# clock_motherboard.net
KiCad netlist of a schematic drawn in EAGLE
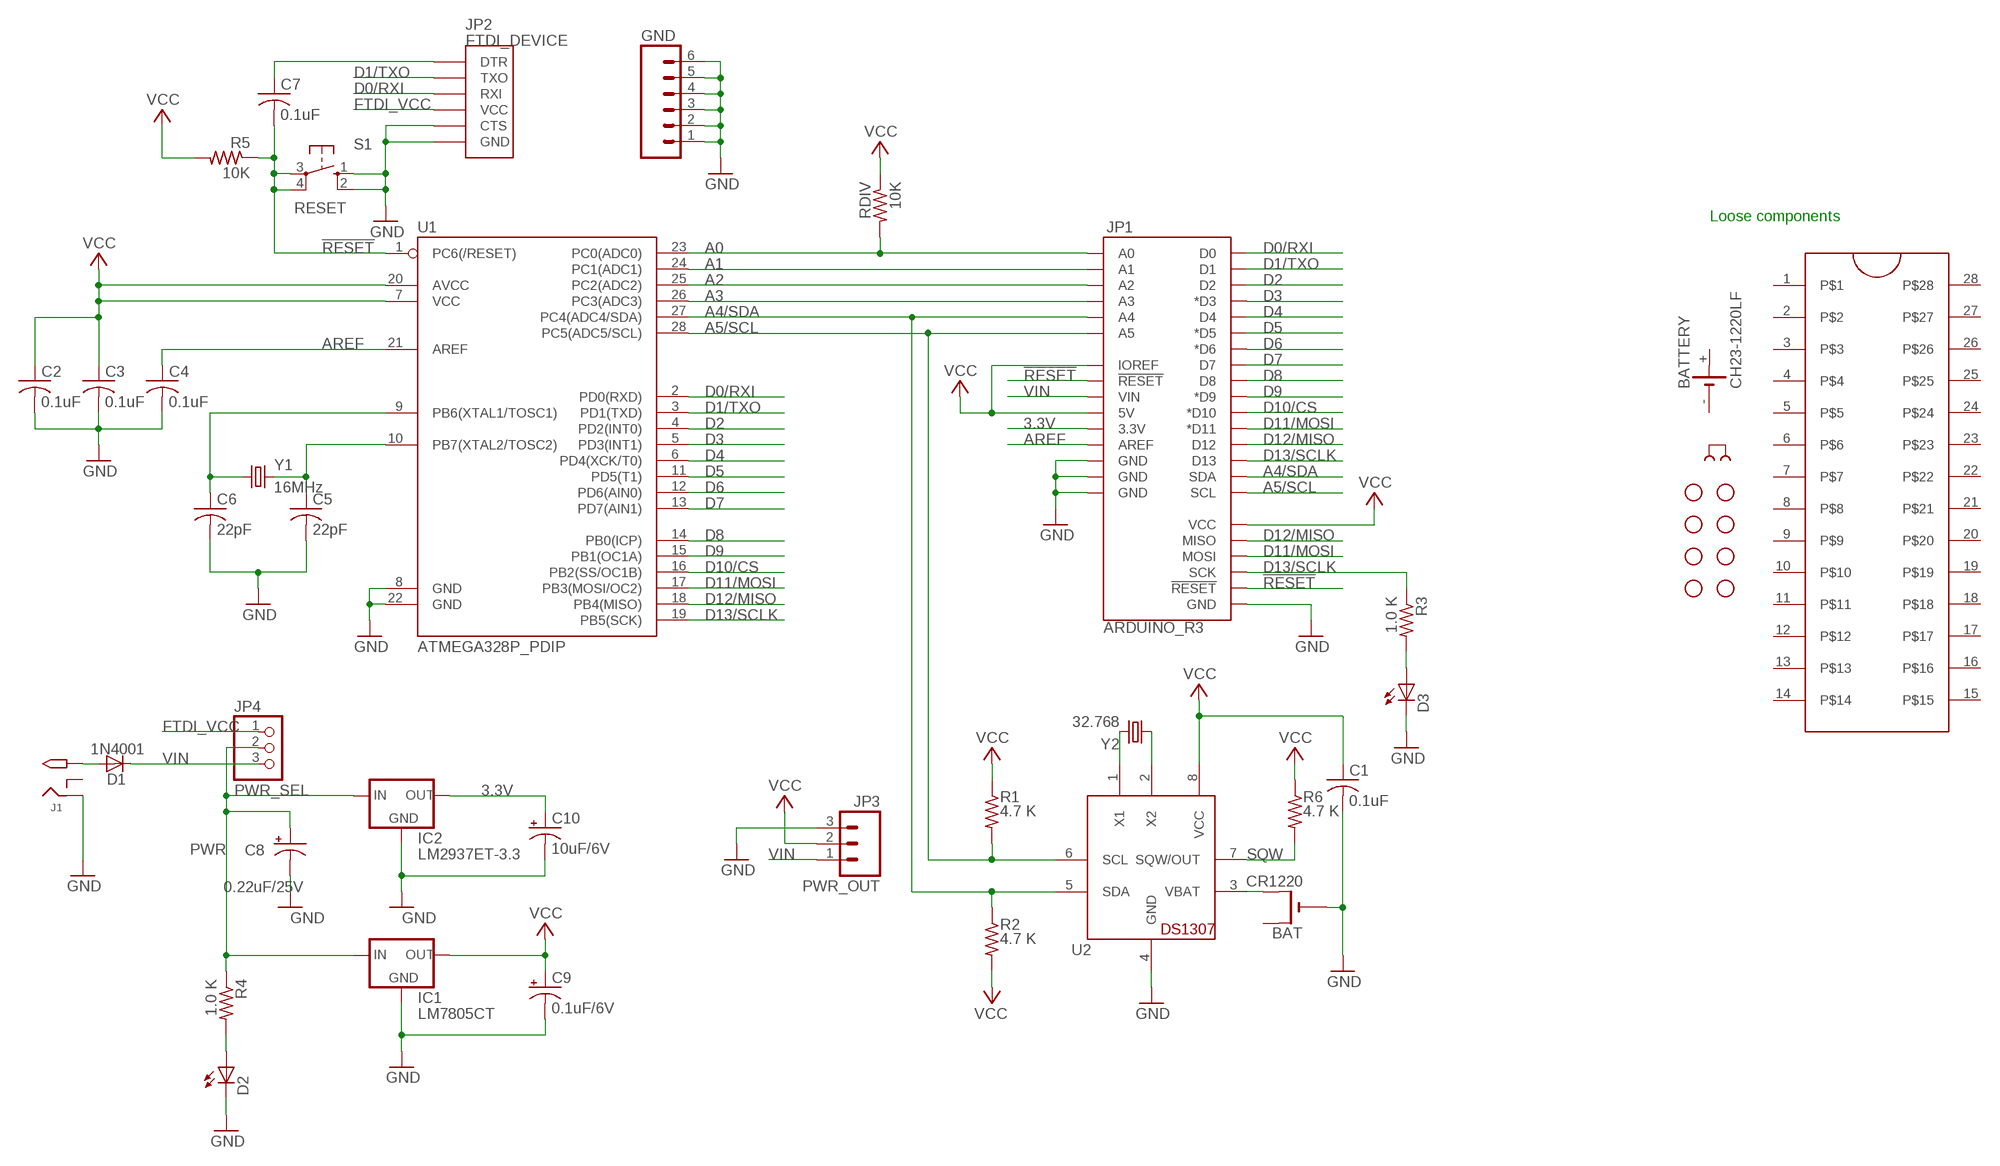
[diagram p0: schematic, sheet 1]

(export (version "E")
  (design (tool "Eeschema 10.0.6"))
  (components
    (comp (ref "BAT")
      (value "CR1220")
      (footprint "eagle-import:CR1220-THM")
      (fields (field (name "PARTNO") "3001"))
      (libsource (lib "eagle-import") (part "CR1220THM"))
    )
    (comp (ref "BATTERY")
      (value "CH23-1220LF")
      (footprint "eagle-import:CH23-1220LF")
      (fields (field (name "PARTNO") "CR1220"))
      (libsource (lib "eagle-import") (part "CH23-1220LF"))
    )
    (comp (ref "C1")
      (value "0.1uF")
      (footprint "eagle-import:C025-025X050")
      (fields (field (name "PARTNO") "21RZ310-RC"))
      (libsource (lib "eagle-import") (part "C-US025-025X050"))
    )
    (comp (ref "C2")
      (value "0.1uF")
      (footprint "eagle-import:C025-025X050")
      (fields (field (name "PARTNO") "21RZ310-RC"))
      (libsource (lib "eagle-import") (part "C-US025-025X050"))
    )
    (comp (ref "C3")
      (value "0.1uF")
      (footprint "eagle-import:C025-025X050")
      (fields (field (name "PARTNO") "21RZ310-RC"))
      (libsource (lib "eagle-import") (part "C-US025-025X050"))
    )
    (comp (ref "C4")
      (value "0.1uF")
      (footprint "eagle-import:C025-025X050")
      (fields (field (name "PARTNO") "21RZ310-RC"))
      (libsource (lib "eagle-import") (part "C-US025-025X050"))
    )
    (comp (ref "C5")
      (value "22pF")
      (footprint "eagle-import:C025-025X050")
      (fields (field (name "PARTNO") "K220J15C0GF5TL2"))
      (libsource (lib "eagle-import") (part "C-US025-025X050"))
    )
    (comp (ref "C6")
      (value "22pF")
      (footprint "eagle-import:C025-025X050")
      (fields (field (name "PARTNO") "K220J15C0GF5TL2"))
      (libsource (lib "eagle-import") (part "C-US025-025X050"))
    )
    (comp (ref "C7")
      (value "0.1uF")
      (footprint "eagle-import:C025-025X050")
      (fields (field (name "PARTNO") "21RZ310-RC"))
      (libsource (lib "eagle-import") (part "C-US025-025X050"))
    )
    (comp (ref "C8")
      (value "0.22uF/25V")
      (footprint "eagle-import:E2,5-6")
      (fields (field (name "PARTNO") "FG14X7R1H224KNT06"))
      (libsource (lib "eagle-import") (part "CPOL-USE2.5-6"))
    )
    (comp (ref "C9")
      (value "0.1uF/6V")
      (footprint "eagle-import:E2,5-6")
      (fields (field (name "PARTNO") "21RZ310-RC"))
      (libsource (lib "eagle-import") (part "CPOL-USE2.5-6"))
    )
    (comp (ref "C10")
      (value "10uF/6V")
      (footprint "eagle-import:E2,5-6")
      (fields (field (name "PARTNO") "A758BG106M1EAAE070"))
      (libsource (lib "eagle-import") (part "CPOL-USE2.5-6"))
    )
    (comp (ref "D1")
      (value "1N4001")
      (footprint "eagle-import:DO41-10")
      (fields (field (name "PARTNO") "1N4001-TP"))
      (libsource (lib "eagle-import") (part "1N4004"))
    )
    (comp (ref "D2")
      (value "RED")
      (footprint "eagle-import:LED3MM")
      (fields (field (name "PARTNO") "WP7113SRD/D"))
      (libsource (lib "eagle-import") (part "LED3MM"))
    )
    (comp (ref "D3")
      (value "YELLOW")
      (footprint "eagle-import:LED3MM")
      (fields (field (name "PARTNO") "WP7113SYD"))
      (libsource (lib "eagle-import") (part "LED3MM"))
    )
    (comp (ref "GND")
      (value "M06NO_SILK_FEMALE_PTH")
      (footprint "eagle-import:1X06_NO_SILK")
      (libsource (lib "eagle-import") (part "M06NO_SILK_FEMALE_PTH"))
    )
    (comp (ref "IC1")
      (value "LM7805CT")
      (footprint "eagle-import:78XXS")
      (fields (field (name "PARTNO") "LM7805CT/NOPB"))
      (libsource (lib "eagle-import") (part "78XXS"))
    )
    (comp (ref "IC2")
      (value "LM2937ET-3.3")
      (footprint "eagle-import:78XXS")
      (fields (field (name "PARTNO") "LM2937ET-3.3/NOPB"))
      (libsource (lib "eagle-import") (part "78XXS"))
    )
    (comp (ref "J1")
      (value "2.1MMJACK")
      (footprint "eagle-import:PJ-102A")
      (fields (field (name "PARTNO") "PJ-102AH"))
      (libsource (lib "eagle-import") (part "2.1MMJACK"))
    )
    (comp (ref "J2")
      (value "PWR_SEL")
      (footprint "eagle-import:JUMP")
      (fields (field (name "PARTNO") "382811-8"))
      (libsource (lib "eagle-import") (part "JUMPER"))
    )
    (comp (ref "JP1")
      (value "ARDUINO_R3")
      (footprint "eagle-import:ARDUINO_R3")
      (libsource (lib "eagle-import") (part "ARDUINO_R3"))
    )
    (comp (ref "JP2")
      (value "FTDI_DEVICE")
      (footprint "eagle-import:FTDI_DEVICE_SIDE")
      (fields (field (name "PARTNO") "68000-406HLF"))
      (libsource (lib "eagle-import") (part "FTDI_DEVICE"))
    )
    (comp (ref "JP3")
      (value "PWR_OUT")
      (footprint "eagle-import:SCREWTERMINAL-3.5MM-3")
      (fields (field (name "PARTNO") "1546551-3"))
      (libsource (lib "eagle-import") (part "M03SCREW"))
    )
    (comp (ref "JP4")
      (value "PWR_SEL")
      (footprint "eagle-import:1X03")
      (fields (field (name "PARTNO") "68001-403HLF"))
      (libsource (lib "eagle-import") (part "PINHD-1X3"))
    )
    (comp (ref "R1")
      (value "4.7 K")
      (footprint "eagle-import:0207_5V")
      (fields (field (name "PARTNO") "CFR-25JB-52-4K7"))
      (libsource (lib "eagle-import") (part "R-US_0207/5V"))
    )
    (comp (ref "R2")
      (value "4.7 K")
      (footprint "eagle-import:0207_5V")
      (fields (field (name "PARTNO") "CFR-25JB-52-4K7"))
      (libsource (lib "eagle-import") (part "R-US_0207/5V"))
    )
    (comp (ref "R3")
      (value "1.0 K")
      (footprint "eagle-import:0207_5V")
      (fields (field (name "PARTNO") "CFR-25JB-52-1K"))
      (libsource (lib "eagle-import") (part "R-US_0207/5V"))
    )
    (comp (ref "R4")
      (value "1.0 K")
      (footprint "eagle-import:0207_5V")
      (fields (field (name "PARTNO") "CFR-25JB-52-1K"))
      (libsource (lib "eagle-import") (part "R-US_0207/5V"))
    )
    (comp (ref "R5")
      (value "10K")
      (footprint "eagle-import:0207_5V")
      (fields (field (name "PARTNO") "CFR-25JB-52-10K"))
      (libsource (lib "eagle-import") (part "rcl-ez_R-US_0207/5V"))
    )
    (comp (ref "R6")
      (value "4.7 K")
      (footprint "eagle-import:0207_5V")
      (fields (field (name "PARTNO") "CFR-25JB-52-4K7"))
      (libsource (lib "eagle-import") (part "R-US_0207/5V"))
    )
    (comp (ref "RDIV")
      (value "10K")
      (footprint "eagle-import:0207_5V")
      (fields (field (name "PARTNO") "CFR-25JB-52-10K"))
      (libsource (lib "eagle-import") (part "rcl-ez_R-US_0207/5V"))
    )
    (comp (ref "S1")
      (value "RESET")
      (footprint "eagle-import:B3F-10XX")
      (fields (field (name "MPN") "B3F-1000"))
      (libsource (lib "eagle-import") (part "10-XX"))
    )
    (comp (ref "SOCKET")
      (value "ZIFSOCKET-28-3ZIFFSOCKET-28-3")
      (footprint "eagle-import:DIL28-3-ZIF_SOCKET")
      (fields (field (name "PARTNO") "4828-3004-CP"))
      (libsource (lib "eagle-import") (part "ZIFSOCKET-28-3ZIFFSOCKET-28-3"))
    )
    (comp (ref "STANDOFF1")
      (value "STAND-OFF")
      (footprint "eagle-import:STAND-OFF")
      (fields (field (name "PARTNO") "2200"))
      (libsource (lib "eagle-import") (part "STAND-OFF"))
    )
    (comp (ref "STANDOFF2")
      (value "STAND-OFF")
      (footprint "eagle-import:STAND-OFF")
      (fields (field (name "PARTNO") "2200"))
      (libsource (lib "eagle-import") (part "STAND-OFF"))
    )
    (comp (ref "STANDOFF3")
      (value "STAND-OFF")
      (footprint "eagle-import:STAND-OFF")
      (fields (field (name "PARTNO") "2200"))
      (libsource (lib "eagle-import") (part "STAND-OFF"))
    )
    (comp (ref "STANDOFF4")
      (value "STAND-OFF")
      (footprint "eagle-import:STAND-OFF")
      (fields (field (name "PARTNO") "2200"))
      (libsource (lib "eagle-import") (part "STAND-OFF"))
    )
    (comp (ref "STANDOFF5")
      (value "STAND-OFF")
      (footprint "eagle-import:STAND-OFF")
      (fields (field (name "PARTNO") "9900"))
      (libsource (lib "eagle-import") (part "STAND-OFF"))
    )
    (comp (ref "STANDOFF6")
      (value "STAND-OFF")
      (footprint "eagle-import:STAND-OFF")
      (fields (field (name "PARTNO") "9900"))
      (libsource (lib "eagle-import") (part "STAND-OFF"))
    )
    (comp (ref "STANDOFF7")
      (value "STAND-OFF")
      (footprint "eagle-import:STAND-OFF")
      (fields (field (name "PARTNO") "9900"))
      (libsource (lib "eagle-import") (part "STAND-OFF"))
    )
    (comp (ref "STANDOFF8")
      (value "STAND-OFF")
      (footprint "eagle-import:STAND-OFF")
      (fields (field (name "PARTNO") "9900"))
      (libsource (lib "eagle-import") (part "STAND-OFF"))
    )
    (comp (ref "U1")
      (value "ATMEGA328P_PDIP")
      (footprint "eagle-import:DIL28-3")
      (fields (field (name "PARTNO") "ATMEGA328P-PU"))
      (libsource (lib "eagle-import") (part "ATMEGA328P_PDIP"))
    )
    (comp (ref "U2")
      (value "DS1307")
      (footprint "eagle-import:DIL08")
      (fields (field (name "PARTNO") "DS1307+"))
      (libsource (lib "eagle-import") (part "DS1307"))
    )
    (comp (ref "Y1")
      (value "16MHz")
      (footprint "eagle-import:HC49US")
      (fields (field (name "PARTNO") "HC49US-16.000MABJ-UB"))
      (libsource (lib "eagle-import") (part "CRYSTALHC49US"))
    )
    (comp (ref "Y2")
      (value "32.768")
      (footprint "eagle-import:TC38H")
      (fields (field (name "PARTNO") "AB38T-32.768KHZ"))
      (libsource (lib "eagle-import") (part "CRYTALTC38H"))
    )
  )
  (nets
    (net (code "1") (name "/3.3V") (class "Default")
      (node (ref "C10") (pin "+") (pinfunction "+_+") (pintype "passive"))
      (node (ref "IC2") (pin "OUT") (pinfunction "OUT_OUT") (pintype "passive"))
      (node (ref "JP1") (pin "3.3V") (pinfunction "3.3V_3.3V") (pintype "bidirectional"))
    )
    (net (code "2") (name "/A0") (class "Default")
      (node (ref "JP1") (pin "A0") (pinfunction "A0_A0") (pintype "bidirectional"))
      (node (ref "RDIV") (pin "2") (pinfunction "2_2") (pintype "passive"))
      (node (ref "U1") (pin "23") (pinfunction "PC0(ADC0)_23") (pintype "bidirectional"))
    )
    (net (code "3") (name "/A1") (class "Default")
      (node (ref "JP1") (pin "A1") (pinfunction "A1_A1") (pintype "bidirectional"))
      (node (ref "U1") (pin "24") (pinfunction "PC1(ADC1)_24") (pintype "bidirectional"))
    )
    (net (code "4") (name "/A2") (class "Default")
      (node (ref "JP1") (pin "A2") (pinfunction "A2_A2") (pintype "bidirectional"))
      (node (ref "U1") (pin "25") (pinfunction "PC2(ADC2)_25") (pintype "bidirectional"))
    )
    (net (code "5") (name "/A3") (class "Default")
      (node (ref "JP1") (pin "A3") (pinfunction "A3_A3") (pintype "bidirectional"))
      (node (ref "U1") (pin "26") (pinfunction "PC3(ADC3)_26") (pintype "bidirectional"))
    )
    (net (code "6") (name "/A4{slash}SDA") (class "Default")
      (node (ref "JP1") (pin "A4") (pinfunction "A4_A4") (pintype "bidirectional"))
      (node (ref "JP1") (pin "SDA") (pinfunction "SDA_SDA") (pintype "bidirectional"))
      (node (ref "R2") (pin "1") (pinfunction "1_1") (pintype "passive"))
      (node (ref "U1") (pin "27") (pinfunction "PC4(ADC4/SDA)_27") (pintype "bidirectional"))
      (node (ref "U2") (pin "5") (pinfunction "SDA_5") (pintype "bidirectional"))
    )
    (net (code "7") (name "/A5{slash}SCL") (class "Default")
      (node (ref "JP1") (pin "A5") (pinfunction "A5_A5") (pintype "bidirectional"))
      (node (ref "JP1") (pin "SCL") (pinfunction "SCL_SCL") (pintype "bidirectional"))
      (node (ref "R1") (pin "2") (pinfunction "2_2") (pintype "passive"))
      (node (ref "U1") (pin "28") (pinfunction "PC5(ADC5/SCL)_28") (pintype "bidirectional"))
      (node (ref "U2") (pin "6") (pinfunction "SCL_6") (pintype "bidirectional"))
    )
    (net (code "8") (name "/AREF") (class "Default")
      (node (ref "C4") (pin "1") (pinfunction "1_1") (pintype "passive"))
      (node (ref "JP1") (pin "AREF") (pinfunction "AREF_AREF") (pintype "bidirectional"))
      (node (ref "U1") (pin "21") (pinfunction "AREF_21") (pintype "bidirectional"))
    )
    (net (code "9") (name "/D0{slash}RXI") (class "Default")
      (node (ref "JP1") (pin "D0") (pinfunction "D0_D0") (pintype "bidirectional"))
      (node (ref "JP2") (pin "P$3") (pinfunction "RXI_P$3") (pintype "bidirectional"))
      (node (ref "U1") (pin "2") (pinfunction "PD0(RXD)_2") (pintype "bidirectional"))
    )
    (net (code "10") (name "/D1{slash}TXO") (class "Default")
      (node (ref "JP1") (pin "D1") (pinfunction "D1_D1") (pintype "bidirectional"))
      (node (ref "JP2") (pin "P$2") (pinfunction "TXO_P$2") (pintype "bidirectional"))
      (node (ref "U1") (pin "3") (pinfunction "PD1(TXD)_3") (pintype "bidirectional"))
    )
    (net (code "11") (name "/D2") (class "Default")
      (node (ref "JP1") (pin "D2") (pinfunction "D2_D2") (pintype "bidirectional"))
      (node (ref "U1") (pin "4") (pinfunction "PD2(INT0)_4") (pintype "bidirectional"))
    )
    (net (code "12") (name "/D3") (class "Default")
      (node (ref "JP1") (pin "D3") (pinfunction "*D3_D3") (pintype "bidirectional"))
      (node (ref "U1") (pin "5") (pinfunction "PD3(INT1)_5") (pintype "bidirectional"))
    )
    (net (code "13") (name "/D4") (class "Default")
      (node (ref "JP1") (pin "D4") (pinfunction "D4_D4") (pintype "bidirectional"))
      (node (ref "U1") (pin "6") (pinfunction "PD4(XCK/T0)_6") (pintype "bidirectional"))
    )
    (net (code "14") (name "/D5") (class "Default")
      (node (ref "JP1") (pin "D5") (pinfunction "*D5_D5") (pintype "bidirectional"))
      (node (ref "U1") (pin "11") (pinfunction "PD5(T1)_11") (pintype "bidirectional"))
    )
    (net (code "15") (name "/D6") (class "Default")
      (node (ref "JP1") (pin "D6") (pinfunction "*D6_D6") (pintype "bidirectional"))
      (node (ref "U1") (pin "12") (pinfunction "PD6(AIN0)_12") (pintype "bidirectional"))
    )
    (net (code "16") (name "/D7") (class "Default")
      (node (ref "JP1") (pin "D7") (pinfunction "D7_D7") (pintype "bidirectional"))
      (node (ref "U1") (pin "13") (pinfunction "PD7(AIN1)_13") (pintype "bidirectional"))
    )
    (net (code "17") (name "/D8") (class "Default")
      (node (ref "JP1") (pin "D8") (pinfunction "D8_D8") (pintype "bidirectional"))
      (node (ref "U1") (pin "14") (pinfunction "PB0(ICP)_14") (pintype "bidirectional"))
    )
    (net (code "18") (name "/D9") (class "Default")
      (node (ref "JP1") (pin "D9") (pinfunction "*D9_D9") (pintype "bidirectional"))
      (node (ref "U1") (pin "15") (pinfunction "PB1(OC1A)_15") (pintype "bidirectional"))
    )
    (net (code "19") (name "/D10{slash}CS") (class "Default")
      (node (ref "JP1") (pin "D10") (pinfunction "*D10_D10") (pintype "bidirectional"))
      (node (ref "U1") (pin "16") (pinfunction "PB2(SS/OC1B)_16") (pintype "bidirectional"))
    )
    (net (code "20") (name "/D11{slash}MOSI") (class "Default")
      (node (ref "JP1") (pin "D11") (pinfunction "*D11_D11") (pintype "bidirectional"))
      (node (ref "JP1") (pin "MOSI") (pinfunction "MOSI_MOSI") (pintype "bidirectional"))
      (node (ref "U1") (pin "17") (pinfunction "PB3(MOSI/OC2)_17") (pintype "bidirectional"))
    )
    (net (code "21") (name "/D12{slash}MISO") (class "Default")
      (node (ref "JP1") (pin "D12") (pinfunction "D12_D12") (pintype "bidirectional"))
      (node (ref "JP1") (pin "MISO") (pinfunction "MISO_MISO") (pintype "bidirectional"))
      (node (ref "U1") (pin "18") (pinfunction "PB4(MISO)_18") (pintype "bidirectional"))
    )
    (net (code "22") (name "/D13{slash}SCLK") (class "Default")
      (node (ref "JP1") (pin "D13") (pinfunction "D13_D13") (pintype "bidirectional"))
      (node (ref "JP1") (pin "SCK") (pinfunction "SCK_SCK") (pintype "bidirectional"))
      (node (ref "R3") (pin "1") (pinfunction "1_1") (pintype "passive"))
      (node (ref "U1") (pin "19") (pinfunction "PB5(SCK)_19") (pintype "bidirectional"))
    )
    (net (code "23") (name "/FTDI_VCC") (class "Default")
      (node (ref "JP2") (pin "P$4") (pinfunction "VCC_P$4") (pintype "bidirectional"))
      (node (ref "JP4") (pin "1") (pinfunction "1_1") (pintype "passive"))
    )
    (net (code "24") (name "/PWR") (class "Default")
      (node (ref "C8") (pin "+") (pinfunction "+_+") (pintype "passive"))
      (node (ref "IC1") (pin "IN") (pinfunction "IN_IN") (pintype "input"))
      (node (ref "IC2") (pin "IN") (pinfunction "IN_IN") (pintype "input"))
      (node (ref "JP4") (pin "2") (pinfunction "2_2") (pintype "passive"))
      (node (ref "R4") (pin "1") (pinfunction "1_1") (pintype "passive"))
    )
    (net (code "25") (name "/SQW") (class "Default")
      (node (ref "R6") (pin "2") (pinfunction "2_2") (pintype "passive"))
      (node (ref "U2") (pin "7") (pinfunction "SQW/OUT_7") (pintype "bidirectional"))
    )
    (net (code "26") (name "/VIN") (class "Default")
      (node (ref "D1") (pin "C") (pinfunction "C_C") (pintype "passive"))
      (node (ref "JP1") (pin "VIN") (pinfunction "VIN_VIN") (pintype "bidirectional"))
      (node (ref "JP3") (pin "1") (pinfunction "1_1") (pintype "passive"))
      (node (ref "JP4") (pin "3") (pinfunction "3_3") (pintype "passive"))
    )
    (net (code "27") (name "/~{RESET}") (class "Default")
      (node (ref "C7") (pin "2") (pinfunction "2_2") (pintype "passive"))
      (node (ref "JP1") (pin "RESET@1") (pinfunction "~{RESET}_RESET@1") (pintype "bidirectional"))
      (node (ref "JP1") (pin "RESET@2") (pinfunction "~{RESET}_RESET@2") (pintype "bidirectional"))
      (node (ref "R5") (pin "1") (pinfunction "1_1") (pintype "passive"))
      (node (ref "S1") (pin "3") (pinfunction "P_3") (pintype "passive"))
      (node (ref "S1") (pin "4") (pinfunction "P1_4") (pintype "passive"))
      (node (ref "U1") (pin "1") (pinfunction "PC6(/RESET)_1") (pintype "bidirectional"))
    )
    (net (code "28") (name "GND") (class "Default")
      (node (ref "BAT") (pin "-") (pinfunction "-_-") (pintype "passive"))
      (node (ref "C1") (pin "2") (pinfunction "2_2") (pintype "passive"))
      (node (ref "C10") (pin "-") (pinfunction "-_-") (pintype "passive"))
      (node (ref "C2") (pin "2") (pinfunction "2_2") (pintype "passive"))
      (node (ref "C3") (pin "2") (pinfunction "2_2") (pintype "passive"))
      (node (ref "C4") (pin "2") (pinfunction "2_2") (pintype "passive"))
      (node (ref "C5") (pin "2") (pinfunction "2_2") (pintype "passive"))
      (node (ref "C6") (pin "2") (pinfunction "2_2") (pintype "passive"))
      (node (ref "C8") (pin "-") (pinfunction "-_-") (pintype "passive"))
      (node (ref "C9") (pin "-") (pinfunction "-_-") (pintype "passive"))
      (node (ref "D2") (pin "K") (pinfunction "C_K") (pintype "passive"))
      (node (ref "D3") (pin "K") (pinfunction "C_K") (pintype "passive"))
      (node (ref "GND") (pin "1") (pinfunction "1_1") (pintype "passive"))
      (node (ref "GND") (pin "2") (pinfunction "2_2") (pintype "passive"))
      (node (ref "GND") (pin "3") (pinfunction "3_3") (pintype "passive"))
      (node (ref "GND") (pin "4") (pinfunction "4_4") (pintype "passive"))
      (node (ref "GND") (pin "5") (pinfunction "5_5") (pintype "passive"))
      (node (ref "GND") (pin "6") (pinfunction "6_6") (pintype "passive"))
      (node (ref "IC1") (pin "GND") (pinfunction "GND_GND") (pintype "input"))
      (node (ref "IC2") (pin "GND") (pinfunction "GND_GND") (pintype "input"))
      (node (ref "J1") (pin "RING") (pinfunction "RING_RING") (pintype "bidirectional"))
      (node (ref "JP1") (pin "GND@1") (pinfunction "GND_GND@1") (pintype "bidirectional"))
      (node (ref "JP1") (pin "GND@2") (pinfunction "GND_GND@2") (pintype "bidirectional"))
      (node (ref "JP1") (pin "GND@3") (pinfunction "GND_GND@3") (pintype "bidirectional"))
      (node (ref "JP1") (pin "GND@4") (pinfunction "GND_GND@4") (pintype "bidirectional"))
      (node (ref "JP2") (pin "P$5") (pinfunction "CTS_P$5") (pintype "bidirectional"))
      (node (ref "JP2") (pin "P$6") (pinfunction "GND_P$6") (pintype "bidirectional"))
      (node (ref "JP3") (pin "3") (pinfunction "3_3") (pintype "passive"))
      (node (ref "S1") (pin "1") (pinfunction "S_1") (pintype "passive"))
      (node (ref "S1") (pin "2") (pinfunction "S1_2") (pintype "passive"))
      (node (ref "U1") (pin "22") (pinfunction "GND_22") (pintype "bidirectional"))
      (node (ref "U1") (pin "8") (pinfunction "GND_8") (pintype "bidirectional"))
      (node (ref "U2") (pin "4") (pinfunction "GND_4") (pintype "power_in"))
    )
    (net (code "29") (name "Net-(BAT-+1)") (class "Default")
      (node (ref "BAT") (pin "+2") (pinfunction "+1_+2") (pintype "passive"))
      (node (ref "U2") (pin "3") (pinfunction "VBAT_3") (pintype "power_in"))
    )
    (net (code "30") (name "Net-(D1-PadA)") (class "Default")
      (node (ref "D1") (pin "A") (pinfunction "A_A") (pintype "passive"))
      (node (ref "J1") (pin "TIP") (pinfunction "TIP_TIP") (pintype "bidirectional"))
    )
    (net (code "31") (name "Net-(D2-PadA)") (class "Default")
      (node (ref "D2") (pin "A") (pinfunction "A_A") (pintype "passive"))
      (node (ref "R4") (pin "2") (pinfunction "2_2") (pintype "passive"))
    )
    (net (code "32") (name "Net-(D3-PadA)") (class "Default")
      (node (ref "D3") (pin "A") (pinfunction "A_A") (pintype "passive"))
      (node (ref "R3") (pin "2") (pinfunction "2_2") (pintype "passive"))
    )
    (net (code "33") (name "Net-(JP2-DTR)") (class "Default")
      (node (ref "C7") (pin "1") (pinfunction "1_1") (pintype "passive"))
      (node (ref "JP2") (pin "P$1") (pinfunction "DTR_P$1") (pintype "bidirectional"))
    )
    (net (code "34") (name "Net-(U1-PB6(XTAL1{slash}TOSC1))") (class "Default")
      (node (ref "C6") (pin "1") (pinfunction "1_1") (pintype "passive"))
      (node (ref "U1") (pin "9") (pinfunction "PB6(XTAL1/TOSC1)_9") (pintype "bidirectional"))
      (node (ref "Y1") (pin "1") (pinfunction "1_1") (pintype "passive"))
    )
    (net (code "35") (name "Net-(U1-PB7(XTAL2{slash}TOSC2))") (class "Default")
      (node (ref "C5") (pin "1") (pinfunction "1_1") (pintype "passive"))
      (node (ref "U1") (pin "10") (pinfunction "PB7(XTAL2/TOSC2)_10") (pintype "bidirectional"))
      (node (ref "Y1") (pin "2") (pinfunction "2_2") (pintype "passive"))
    )
    (net (code "36") (name "Net-(U2-X1)") (class "Default")
      (node (ref "U2") (pin "1") (pinfunction "X1_1") (pintype "passive"))
      (node (ref "Y2") (pin "2") (pinfunction "2_2") (pintype "passive"))
    )
    (net (code "37") (name "Net-(U2-X2)") (class "Default")
      (node (ref "U2") (pin "2") (pinfunction "X2_2") (pintype "passive"))
      (node (ref "Y2") (pin "1") (pinfunction "1_1") (pintype "passive"))
    )
    (net (code "38") (name "VCC") (class "Default")
      (node (ref "C1") (pin "1") (pinfunction "1_1") (pintype "passive"))
      (node (ref "C2") (pin "1") (pinfunction "1_1") (pintype "passive"))
      (node (ref "C3") (pin "1") (pinfunction "1_1") (pintype "passive"))
      (node (ref "C9") (pin "+") (pinfunction "+_+") (pintype "passive"))
      (node (ref "IC1") (pin "OUT") (pinfunction "OUT_OUT") (pintype "passive"))
      (node (ref "JP1") (pin "5V") (pinfunction "5V_5V") (pintype "bidirectional"))
      (node (ref "JP1") (pin "IOREF") (pinfunction "IOREF_IOREF") (pintype "bidirectional"))
      (node (ref "JP1") (pin "VCC") (pinfunction "VCC_VCC") (pintype "bidirectional"))
      (node (ref "JP3") (pin "2") (pinfunction "2_2") (pintype "passive"))
      (node (ref "R1") (pin "1") (pinfunction "1_1") (pintype "passive"))
      (node (ref "R2") (pin "2") (pinfunction "2_2") (pintype "passive"))
      (node (ref "R5") (pin "2") (pinfunction "2_2") (pintype "passive"))
      (node (ref "R6") (pin "1") (pinfunction "1_1") (pintype "passive"))
      (node (ref "RDIV") (pin "1") (pinfunction "1_1") (pintype "passive"))
      (node (ref "U1") (pin "20") (pinfunction "AVCC_20") (pintype "bidirectional"))
      (node (ref "U1") (pin "7") (pinfunction "VCC_7") (pintype "bidirectional"))
      (node (ref "U2") (pin "8") (pinfunction "VCC_8") (pintype "power_in"))
    )
    (net (code "39") (name "unconnected-(BAT-+-Pad+1)") (class "Default")
      (node (ref "BAT") (pin "+1") (pinfunction "+_+1") (pintype "passive"))
    )
    (net (code "40") (name "unconnected-(BATTERY-Pad+)") (class "Default")
      (node (ref "BATTERY") (pin "+") (pinfunction "+_+") (pintype "passive"))
    )
    (net (code "41") (name "unconnected-(BATTERY-Pad-)") (class "Default")
      (node (ref "BATTERY") (pin "-") (pinfunction "-_-") (pintype "passive"))
    )
    (net (code "42") (name "unconnected-(J1-PadRING_SW)") (class "Default")
      (node (ref "J1") (pin "RING_SW") (pinfunction "RING_SW_RING_SW") (pintype "bidirectional"))
    )
    (net (code "43") (name "unconnected-(SOCKET-P$1-Pad1)") (class "Default")
      (node (ref "SOCKET") (pin "1") (pinfunction "P$1_1") (pintype "bidirectional"))
    )
    (net (code "44") (name "unconnected-(SOCKET-P$2-Pad2)") (class "Default")
      (node (ref "SOCKET") (pin "2") (pinfunction "P$2_2") (pintype "bidirectional"))
    )
    (net (code "45") (name "unconnected-(SOCKET-P$3-Pad3)") (class "Default")
      (node (ref "SOCKET") (pin "3") (pinfunction "P$3_3") (pintype "bidirectional"))
    )
    (net (code "46") (name "unconnected-(SOCKET-P$4-Pad4)") (class "Default")
      (node (ref "SOCKET") (pin "4") (pinfunction "P$4_4") (pintype "bidirectional"))
    )
    (net (code "47") (name "unconnected-(SOCKET-P$5-Pad5)") (class "Default")
      (node (ref "SOCKET") (pin "5") (pinfunction "P$5_5") (pintype "bidirectional"))
    )
    (net (code "48") (name "unconnected-(SOCKET-P$6-Pad6)") (class "Default")
      (node (ref "SOCKET") (pin "6") (pinfunction "P$6_6") (pintype "bidirectional"))
    )
    (net (code "49") (name "unconnected-(SOCKET-P$7-Pad7)") (class "Default")
      (node (ref "SOCKET") (pin "7") (pinfunction "P$7_7") (pintype "bidirectional"))
    )
    (net (code "50") (name "unconnected-(SOCKET-P$8-Pad8)") (class "Default")
      (node (ref "SOCKET") (pin "8") (pinfunction "P$8_8") (pintype "bidirectional"))
    )
    (net (code "51") (name "unconnected-(SOCKET-P$9-Pad9)") (class "Default")
      (node (ref "SOCKET") (pin "9") (pinfunction "P$9_9") (pintype "bidirectional"))
    )
    (net (code "52") (name "unconnected-(SOCKET-P$10-Pad10)") (class "Default")
      (node (ref "SOCKET") (pin "10") (pinfunction "P$10_10") (pintype "bidirectional"))
    )
    (net (code "53") (name "unconnected-(SOCKET-P$11-Pad11)") (class "Default")
      (node (ref "SOCKET") (pin "11") (pinfunction "P$11_11") (pintype "bidirectional"))
    )
    (net (code "54") (name "unconnected-(SOCKET-P$12-Pad12)") (class "Default")
      (node (ref "SOCKET") (pin "12") (pinfunction "P$12_12") (pintype "bidirectional"))
    )
    (net (code "55") (name "unconnected-(SOCKET-P$13-Pad13)") (class "Default")
      (node (ref "SOCKET") (pin "13") (pinfunction "P$13_13") (pintype "bidirectional"))
    )
    (net (code "56") (name "unconnected-(SOCKET-P$14-Pad14)") (class "Default")
      (node (ref "SOCKET") (pin "14") (pinfunction "P$14_14") (pintype "bidirectional"))
    )
    (net (code "57") (name "unconnected-(SOCKET-P$15-Pad15)") (class "Default")
      (node (ref "SOCKET") (pin "15") (pinfunction "P$15_15") (pintype "bidirectional"))
    )
    (net (code "58") (name "unconnected-(SOCKET-P$16-Pad16)") (class "Default")
      (node (ref "SOCKET") (pin "16") (pinfunction "P$16_16") (pintype "bidirectional"))
    )
    (net (code "59") (name "unconnected-(SOCKET-P$17-Pad17)") (class "Default")
      (node (ref "SOCKET") (pin "17") (pinfunction "P$17_17") (pintype "bidirectional"))
    )
    (net (code "60") (name "unconnected-(SOCKET-P$18-Pad18)") (class "Default")
      (node (ref "SOCKET") (pin "18") (pinfunction "P$18_18") (pintype "bidirectional"))
    )
    (net (code "61") (name "unconnected-(SOCKET-P$19-Pad19)") (class "Default")
      (node (ref "SOCKET") (pin "19") (pinfunction "P$19_19") (pintype "bidirectional"))
    )
    (net (code "62") (name "unconnected-(SOCKET-P$20-Pad20)") (class "Default")
      (node (ref "SOCKET") (pin "20") (pinfunction "P$20_20") (pintype "bidirectional"))
    )
    (net (code "63") (name "unconnected-(SOCKET-P$21-Pad21)") (class "Default")
      (node (ref "SOCKET") (pin "21") (pinfunction "P$21_21") (pintype "bidirectional"))
    )
    (net (code "64") (name "unconnected-(SOCKET-P$22-Pad22)") (class "Default")
      (node (ref "SOCKET") (pin "22") (pinfunction "P$22_22") (pintype "bidirectional"))
    )
    (net (code "65") (name "unconnected-(SOCKET-P$23-Pad23)") (class "Default")
      (node (ref "SOCKET") (pin "23") (pinfunction "P$23_23") (pintype "bidirectional"))
    )
    (net (code "66") (name "unconnected-(SOCKET-P$24-Pad24)") (class "Default")
      (node (ref "SOCKET") (pin "24") (pinfunction "P$24_24") (pintype "bidirectional"))
    )
    (net (code "67") (name "unconnected-(SOCKET-P$25-Pad25)") (class "Default")
      (node (ref "SOCKET") (pin "25") (pinfunction "P$25_25") (pintype "bidirectional"))
    )
    (net (code "68") (name "unconnected-(SOCKET-P$26-Pad26)") (class "Default")
      (node (ref "SOCKET") (pin "26") (pinfunction "P$26_26") (pintype "bidirectional"))
    )
    (net (code "69") (name "unconnected-(SOCKET-P$27-Pad27)") (class "Default")
      (node (ref "SOCKET") (pin "27") (pinfunction "P$27_27") (pintype "bidirectional"))
    )
    (net (code "70") (name "unconnected-(SOCKET-P$28-Pad28)") (class "Default")
      (node (ref "SOCKET") (pin "28") (pinfunction "P$28_28") (pintype "bidirectional"))
    )
  )
)
